# MJ828_-_prod.net
KiCad netlist of a schematic drawn in EAGLE
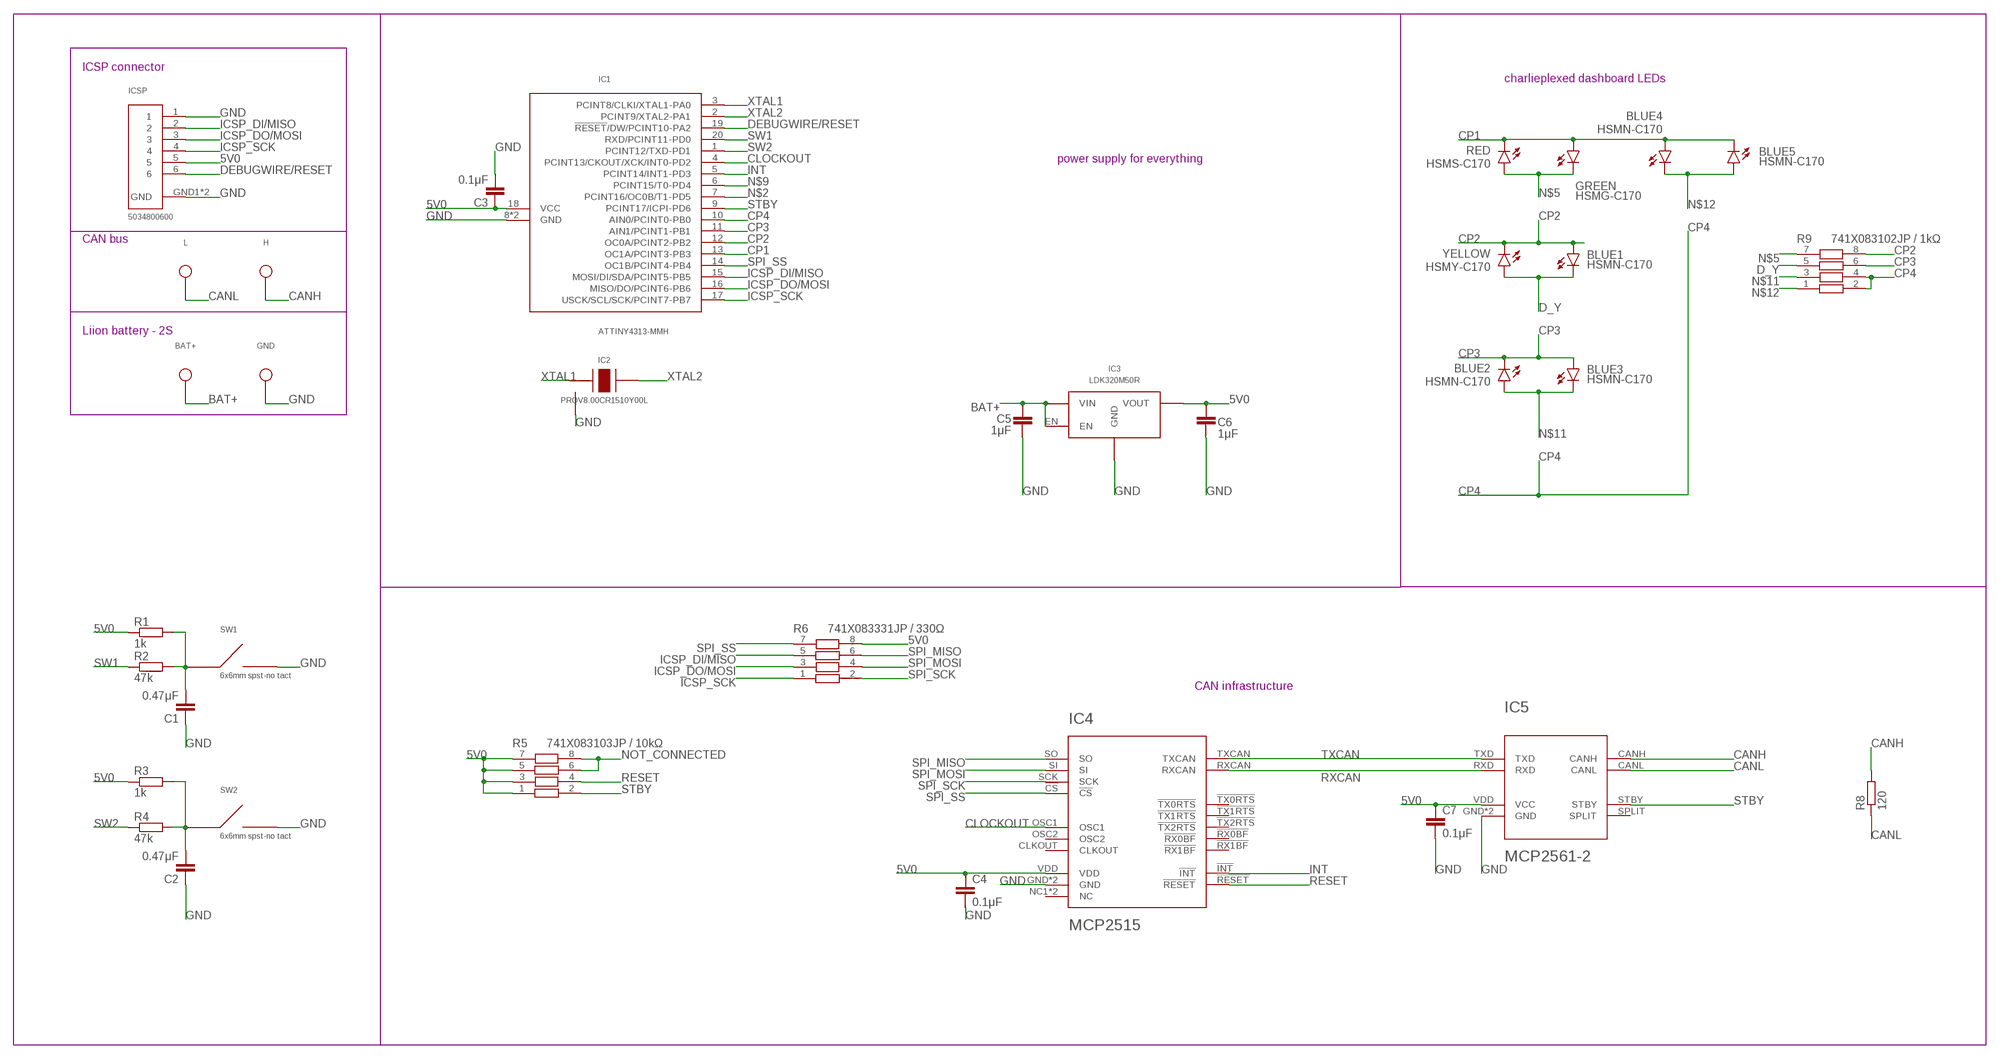
[diagram p0: schematic, sheet 1]

(export (version "E")
  (design (tool "Eeschema 10.0.6"))
  (components
    (comp (ref "BAT+")
      (value "8V4 Battery +")
      (footprint "eagle-import:TH-0.9MM")
      (libsource (lib "eagle-import") (part "TPTH-0.9MM"))
    )
    (comp (ref "BLUE1")
      (value "HSMN-C170")
      (footprint "eagle-import:SML0805")
      (libsource (lib "eagle-import") (part "LEDSML0805"))
    )
    (comp (ref "BLUE2")
      (value "HSMN-C170")
      (footprint "eagle-import:SML0805")
      (libsource (lib "eagle-import") (part "LEDSML0805"))
    )
    (comp (ref "BLUE3")
      (value "HSMN-C170")
      (footprint "eagle-import:SML0805")
      (libsource (lib "eagle-import") (part "LEDSML0805"))
    )
    (comp (ref "BLUE4")
      (value "HSMN-C170")
      (footprint "eagle-import:SML0805")
      (libsource (lib "eagle-import") (part "LEDSML0805"))
    )
    (comp (ref "BLUE5")
      (value "HSMN-C170")
      (footprint "eagle-import:SML0805")
      (libsource (lib "eagle-import") (part "LEDSML0805"))
    )
    (comp (ref "C1")
      (value "0.47μF")
      (footprint "eagle-import:C0402")
      (libsource (lib "eagle-import") (part "C-EUC0402"))
    )
    (comp (ref "C2")
      (value "0.47μF")
      (footprint "eagle-import:C0402")
      (libsource (lib "eagle-import") (part "C-EUC0402"))
    )
    (comp (ref "C3")
      (value "0.1μF")
      (footprint "eagle-import:C0402")
      (libsource (lib "eagle-import") (part "C-EUC0402"))
    )
    (comp (ref "C4")
      (value "0.1μF")
      (footprint "eagle-import:C0402")
      (libsource (lib "eagle-import") (part "C-EUC0402"))
    )
    (comp (ref "C5")
      (value "1μF")
      (footprint "eagle-import:C0402")
      (libsource (lib "eagle-import") (part "C-EUC0402"))
    )
    (comp (ref "C6")
      (value "1μF")
      (footprint "eagle-import:C0402")
      (libsource (lib "eagle-import") (part "C-EUC0402"))
    )
    (comp (ref "C7")
      (value "0.1μF")
      (footprint "eagle-import:C0402")
      (libsource (lib "eagle-import") (part "C-EUC0402"))
    )
    (comp (ref "GND")
      (value "Ground")
      (footprint "eagle-import:TH-0.9MM")
      (libsource (lib "eagle-import") (part "TPTH-0.9MM"))
    )
    (comp (ref "GREEN")
      (value "HSMG-C170")
      (footprint "eagle-import:SML0805")
      (libsource (lib "eagle-import") (part "LEDSML0805"))
    )
    (comp (ref "H")
      (value "CAN High")
      (footprint "eagle-import:TH-0.9MM")
      (libsource (lib "eagle-import") (part "TPTH-0.9MM"))
    )
    (comp (ref "IC1")
      (value "ATTINY4313-MMH")
      (footprint "eagle-import:VQFN-20")
      (fields (field (name "SPICEPREFIX") "X"))
      (libsource (lib "eagle-import") (part "ATTINY4313VQFN-20"))
    )
    (comp (ref "IC2")
      (value "PRQV8.00CR1510Y00L")
      (footprint "eagle-import:SMT")
      (libsource (lib "eagle-import") (part "PRQV"))
    )
    (comp (ref "IC3")
      (value "LDK320M50R")
      (footprint "eagle-import:SOT-23-5L")
      (libsource (lib "eagle-import") (part "LDK320SOT-23-5L"))
    )
    (comp (ref "IC4")
      (value "MCP2515")
      (footprint "eagle-import:QFN20")
      (libsource (lib "eagle-import") (part "MCP2515-I-ML"))
    )
    (comp (ref "IC5")
      (value "MCP2561-2")
      (footprint "eagle-import:DFN10")
      (libsource (lib "eagle-import") (part "MCP2561-2"))
    )
    (comp (ref "ICSP")
      (value "5034800600")
      (footprint "eagle-import:SMT")
      (libsource (lib "eagle-import") (part "5034800600"))
    )
    (comp (ref "L")
      (value "CAN Low")
      (footprint "eagle-import:TH-0.9MM")
      (libsource (lib "eagle-import") (part "TPTH-0.9MM"))
    )
    (comp (ref "R1")
      (value "1k")
      (footprint "eagle-import:R0402")
      (libsource (lib "eagle-import") (part "R-EU_R0402"))
    )
    (comp (ref "R2")
      (value "47k")
      (footprint "eagle-import:R0402")
      (libsource (lib "eagle-import") (part "R-EU_R0402"))
    )
    (comp (ref "R3")
      (value "1k")
      (footprint "eagle-import:R0402")
      (libsource (lib "eagle-import") (part "R-EU_R0402"))
    )
    (comp (ref "R4")
      (value "47k")
      (footprint "eagle-import:R0402")
      (libsource (lib "eagle-import") (part "R-EU_R0402"))
    )
    (comp (ref "R5")
      (value "741X083103JP / 10kΩ")
      (footprint "eagle-import:0402")
      (libsource (lib "eagle-import") (part "741X083331JP"))
    )
    (comp (ref "R6")
      (value "741X083331JP / 330Ω")
      (footprint "eagle-import:0402")
      (libsource (lib "eagle-import") (part "741X083331JP"))
    )
    (comp (ref "R8")
      (value "120")
      (footprint "eagle-import:R0402")
      (libsource (lib "eagle-import") (part "R-EU_R0402"))
    )
    (comp (ref "R9")
      (value "741X083102JP / 1kΩ")
      (footprint "eagle-import:0402")
      (libsource (lib "eagle-import") (part "741X083331JP"))
    )
    (comp (ref "RED")
      (value "HSMS-C170")
      (footprint "eagle-import:SML0805")
      (libsource (lib "eagle-import") (part "LEDSML0805"))
    )
    (comp (ref "SW1")
      (value "6x6mm spst-no tact")
      (footprint "eagle-import:SMD")
      (libsource (lib "eagle-import") (part "TL3305-844809"))
    )
    (comp (ref "SW2")
      (value "6x6mm spst-no tact")
      (footprint "eagle-import:SMD")
      (libsource (lib "eagle-import") (part "TL3305-844809"))
    )
    (comp (ref "YELLOW")
      (value "HSMY-C170")
      (footprint "eagle-import:SML0805")
      (libsource (lib "eagle-import") (part "LEDSML0805"))
    )
  )
  (nets
    (net (code "1") (name "/5V0") (class "Default")
      (node (ref "C3") (pin "1") (pinfunction "1_1") (pintype "passive"))
      (node (ref "C4") (pin "1") (pinfunction "1_1") (pintype "passive"))
      (node (ref "C6") (pin "2") (pinfunction "2_2") (pintype "passive"))
      (node (ref "C7") (pin "1") (pinfunction "1_1") (pintype "passive"))
      (node (ref "IC1") (pin "18") (pinfunction "VCC_18") (pintype "bidirectional"))
      (node (ref "IC3") (pin "OUT") (pinfunction "VOUT_OUT") (pintype "bidirectional"))
      (node (ref "IC4") (pin "VDD") (pinfunction "VDD_VDD") (pintype "power_in"))
      (node (ref "IC5") (pin "VDD") (pinfunction "VCC_VDD") (pintype "power_in"))
      (node (ref "ICSP") (pin "5") (pinfunction "5_5") (pintype "bidirectional"))
      (node (ref "R1") (pin "1") (pinfunction "1_1") (pintype "passive"))
      (node (ref "R3") (pin "1") (pinfunction "1_1") (pintype "passive"))
      (node (ref "R5") (pin "1") (pinfunction "1_1") (pintype "bidirectional"))
      (node (ref "R5") (pin "3") (pinfunction "3_3") (pintype "bidirectional"))
      (node (ref "R5") (pin "5") (pinfunction "5_5") (pintype "bidirectional"))
      (node (ref "R5") (pin "7") (pinfunction "7_7") (pintype "bidirectional"))
      (node (ref "R6") (pin "8") (pinfunction "8_8") (pintype "bidirectional"))
    )
    (net (code "2") (name "/BAT+") (class "Default")
      (node (ref "BAT+") (pin "TP$1") (pinfunction "TP$1_TP$1") (pintype "bidirectional"))
      (node (ref "C5") (pin "1") (pinfunction "1_1") (pintype "passive"))
      (node (ref "IC3") (pin "EN") (pinfunction "EN_EN") (pintype "bidirectional"))
      (node (ref "IC3") (pin "IN") (pinfunction "VIN_IN") (pintype "bidirectional"))
    )
    (net (code "3") (name "/CANH") (class "Default")
      (node (ref "H") (pin "TP$1") (pinfunction "TP$1_TP$1") (pintype "bidirectional"))
      (node (ref "IC5") (pin "CANH") (pinfunction "CANH_CANH") (pintype "bidirectional"))
      (node (ref "R8") (pin "2") (pinfunction "2_2") (pintype "passive"))
    )
    (net (code "4") (name "/CANL") (class "Default")
      (node (ref "IC5") (pin "CANL") (pinfunction "CANL_CANL") (pintype "bidirectional"))
      (node (ref "L") (pin "TP$1") (pinfunction "TP$1_TP$1") (pintype "bidirectional"))
      (node (ref "R8") (pin "1") (pinfunction "1_1") (pintype "passive"))
    )
    (net (code "5") (name "/CLOCKOUT") (class "Default")
      (node (ref "IC1") (pin "4") (pinfunction "PCINT13/CKOUT/XCK/INT0-PD2_4") (pintype "bidirectional"))
      (node (ref "IC4") (pin "OSC1") (pinfunction "OSC1_OSC1") (pintype "bidirectional"))
    )
    (net (code "6") (name "/CP1") (class "Default")
      (node (ref "BLUE4") (pin "A") (pinfunction "A_A") (pintype "passive"))
      (node (ref "BLUE5") (pin "C") (pinfunction "C_C") (pintype "passive"))
      (node (ref "GREEN") (pin "A") (pinfunction "A_A") (pintype "passive"))
      (node (ref "IC1") (pin "13") (pinfunction "OC1A/PCINT3-PB3_13") (pintype "bidirectional"))
      (node (ref "RED") (pin "C") (pinfunction "C_C") (pintype "passive"))
    )
    (net (code "7") (name "/CP2") (class "Default")
      (node (ref "BLUE1") (pin "A") (pinfunction "A_A") (pintype "passive"))
      (node (ref "IC1") (pin "12") (pinfunction "OC0A/PCINT2-PB2_12") (pintype "bidirectional"))
      (node (ref "R9") (pin "8") (pinfunction "8_8") (pintype "bidirectional"))
      (node (ref "YELLOW") (pin "C") (pinfunction "C_C") (pintype "passive"))
    )
    (net (code "8") (name "/CP3") (class "Default")
      (node (ref "BLUE2") (pin "C") (pinfunction "C_C") (pintype "passive"))
      (node (ref "BLUE3") (pin "A") (pinfunction "A_A") (pintype "passive"))
      (node (ref "IC1") (pin "11") (pinfunction "AIN1/PCINT1-PB1_11") (pintype "bidirectional"))
      (node (ref "R9") (pin "6") (pinfunction "6_6") (pintype "bidirectional"))
    )
    (net (code "9") (name "/CP4") (class "Default")
      (node (ref "IC1") (pin "10") (pinfunction "AIN0/PCINT0-PB0_10") (pintype "bidirectional"))
      (node (ref "R9") (pin "2") (pinfunction "2_2") (pintype "bidirectional"))
      (node (ref "R9") (pin "4") (pinfunction "4_4") (pintype "bidirectional"))
    )
    (net (code "10") (name "/DEBUGWIRE{slash}RESET") (class "Default")
      (node (ref "IC1") (pin "19") (pinfunction "~{RESET}/DW/PCINT10-PA2_19") (pintype "bidirectional"))
      (node (ref "ICSP") (pin "6") (pinfunction "6_6") (pintype "bidirectional"))
    )
    (net (code "11") (name "/D_Y") (class "Default")
      (node (ref "BLUE1") (pin "C") (pinfunction "C_C") (pintype "passive"))
      (node (ref "R9") (pin "5") (pinfunction "5_5") (pintype "bidirectional"))
      (node (ref "YELLOW") (pin "A") (pinfunction "A_A") (pintype "passive"))
    )
    (net (code "12") (name "/GND") (class "Default")
      (node (ref "C1") (pin "1") (pinfunction "1_1") (pintype "passive"))
      (node (ref "C2") (pin "1") (pinfunction "1_1") (pintype "passive"))
      (node (ref "C3") (pin "2") (pinfunction "2_2") (pintype "passive"))
      (node (ref "C4") (pin "2") (pinfunction "2_2") (pintype "passive"))
      (node (ref "C5") (pin "2") (pinfunction "2_2") (pintype "passive"))
      (node (ref "C6") (pin "1") (pinfunction "1_1") (pintype "passive"))
      (node (ref "C7") (pin "2") (pinfunction "2_2") (pintype "passive"))
      (node (ref "GND") (pin "TP$1") (pinfunction "TP$1_TP$1") (pintype "bidirectional"))
      (node (ref "IC1") (pin "8") (pinfunction "GND_8") (pintype "bidirectional"))
      (node (ref "IC1") (pin "GND") (pinfunction "GND_GND") (pintype "bidirectional"))
      (node (ref "IC2") (pin "GND") (pinfunction "GND_GND") (pintype "bidirectional"))
      (node (ref "IC3") (pin "GND") (pinfunction "GND_GND") (pintype "bidirectional"))
      (node (ref "IC4") (pin "GND") (pinfunction "GND_GND") (pintype "power_in"))
      (node (ref "IC4") (pin "GND6") (pinfunction "GND_GND6") (pintype "power_in"))
      (node (ref "IC5") (pin "GND") (pinfunction "GND_GND") (pintype "power_in"))
      (node (ref "IC5") (pin "VSS") (pinfunction "GND_VSS") (pintype "power_in"))
      (node (ref "ICSP") (pin "1") (pinfunction "1_1") (pintype "bidirectional"))
      (node (ref "ICSP") (pin "GND1") (pinfunction "GND_GND1") (pintype "bidirectional"))
      (node (ref "ICSP") (pin "GND2") (pinfunction "GND_GND2") (pintype "bidirectional"))
      (node (ref "SW1") (pin "3") (pinfunction "P$2_3") (pintype "bidirectional"))
      (node (ref "SW1") (pin "4") (pinfunction "P$2_4") (pintype "bidirectional"))
      (node (ref "SW2") (pin "3") (pinfunction "P$2_3") (pintype "bidirectional"))
      (node (ref "SW2") (pin "4") (pinfunction "P$2_4") (pintype "bidirectional"))
    )
    (net (code "13") (name "/ICSP_DI{slash}MISO") (class "Default")
      (node (ref "IC1") (pin "15") (pinfunction "MOSI/DI/SDA/PCINT5-PB5_15") (pintype "bidirectional"))
      (node (ref "ICSP") (pin "2") (pinfunction "2_2") (pintype "bidirectional"))
      (node (ref "R6") (pin "5") (pinfunction "5_5") (pintype "bidirectional"))
    )
    (net (code "14") (name "/ICSP_DO{slash}MOSI") (class "Default")
      (node (ref "IC1") (pin "16") (pinfunction "MISO/DO/PCINT6-PB6_16") (pintype "bidirectional"))
      (node (ref "ICSP") (pin "3") (pinfunction "3_3") (pintype "bidirectional"))
      (node (ref "R6") (pin "3") (pinfunction "3_3") (pintype "bidirectional"))
    )
    (net (code "15") (name "/ICSP_SCK") (class "Default")
      (node (ref "IC1") (pin "17") (pinfunction "USCK/SCL/SCK/PCINT7-PB7_17") (pintype "bidirectional"))
      (node (ref "ICSP") (pin "4") (pinfunction "4_4") (pintype "bidirectional"))
      (node (ref "R6") (pin "1") (pinfunction "1_1") (pintype "bidirectional"))
    )
    (net (code "16") (name "/INT") (class "Default")
      (node (ref "IC1") (pin "5") (pinfunction "PCINT14/INT1-PD3_5") (pintype "bidirectional"))
      (node (ref "IC4") (pin "!INT!") (pinfunction "~{INT}_!INT!") (pintype "bidirectional"))
    )
    (net (code "17") (name "/N$2") (class "Default")
      (node (ref "IC1") (pin "7") (pinfunction "PCINT16/OC0B/T1-PD5_7") (pintype "bidirectional"))
    )
    (net (code "18") (name "/N$5") (class "Default")
      (node (ref "GREEN") (pin "C") (pinfunction "C_C") (pintype "passive"))
      (node (ref "R9") (pin "7") (pinfunction "7_7") (pintype "bidirectional"))
      (node (ref "RED") (pin "A") (pinfunction "A_A") (pintype "passive"))
    )
    (net (code "19") (name "/N$9") (class "Default")
      (node (ref "IC1") (pin "6") (pinfunction "PCINT15/T0-PD4_6") (pintype "bidirectional"))
    )
    (net (code "20") (name "/N$11") (class "Default")
      (node (ref "BLUE2") (pin "A") (pinfunction "A_A") (pintype "passive"))
      (node (ref "BLUE3") (pin "C") (pinfunction "C_C") (pintype "passive"))
      (node (ref "R9") (pin "3") (pinfunction "3_3") (pintype "bidirectional"))
    )
    (net (code "21") (name "/N$12") (class "Default")
      (node (ref "BLUE4") (pin "C") (pinfunction "C_C") (pintype "passive"))
      (node (ref "BLUE5") (pin "A") (pinfunction "A_A") (pintype "passive"))
      (node (ref "R9") (pin "1") (pinfunction "1_1") (pintype "bidirectional"))
    )
    (net (code "22") (name "/NOT_CONNECTED") (class "Default")
      (node (ref "R5") (pin "6") (pinfunction "6_6") (pintype "bidirectional"))
      (node (ref "R5") (pin "8") (pinfunction "8_8") (pintype "bidirectional"))
    )
    (net (code "23") (name "/RESET") (class "Default")
      (node (ref "IC4") (pin "!RESET!") (pinfunction "~{RESET}_!RESET!") (pintype "bidirectional"))
      (node (ref "R5") (pin "4") (pinfunction "4_4") (pintype "bidirectional"))
    )
    (net (code "24") (name "/RXCAN") (class "Default")
      (node (ref "IC4") (pin "RXCAN") (pinfunction "RXCAN_RXCAN") (pintype "input"))
      (node (ref "IC5") (pin "RXD") (pinfunction "RXD_RXD") (pintype "output"))
    )
    (net (code "25") (name "/SPI_MISO") (class "Default")
      (node (ref "IC4") (pin "SO") (pinfunction "SO_SO") (pintype "output"))
      (node (ref "R6") (pin "6") (pinfunction "6_6") (pintype "bidirectional"))
    )
    (net (code "26") (name "/SPI_MOSI") (class "Default")
      (node (ref "IC4") (pin "SI") (pinfunction "SI_SI") (pintype "input"))
      (node (ref "R6") (pin "4") (pinfunction "4_4") (pintype "bidirectional"))
    )
    (net (code "27") (name "/SPI_SCK") (class "Default")
      (node (ref "IC4") (pin "SCK") (pinfunction "SCK_SCK") (pintype "bidirectional"))
      (node (ref "R6") (pin "2") (pinfunction "2_2") (pintype "bidirectional"))
    )
    (net (code "28") (name "/SPI_SS") (class "Default")
      (node (ref "IC1") (pin "14") (pinfunction "OC1B/PCINT4-PB4_14") (pintype "bidirectional"))
      (node (ref "IC4") (pin "!CS!") (pinfunction "~{CS}_!CS!") (pintype "bidirectional"))
      (node (ref "R6") (pin "7") (pinfunction "7_7") (pintype "bidirectional"))
    )
    (net (code "29") (name "/STBY") (class "Default")
      (node (ref "IC1") (pin "9") (pinfunction "PCINT17/ICPI-PD6_9") (pintype "bidirectional"))
      (node (ref "IC5") (pin "STBY") (pinfunction "STBY_STBY") (pintype "bidirectional"))
      (node (ref "R5") (pin "2") (pinfunction "2_2") (pintype "bidirectional"))
    )
    (net (code "30") (name "/SW1") (class "Default")
      (node (ref "IC1") (pin "20") (pinfunction "RXD/PCINT11-PD0_20") (pintype "bidirectional"))
      (node (ref "R2") (pin "1") (pinfunction "1_1") (pintype "passive"))
    )
    (net (code "31") (name "/SW2") (class "Default")
      (node (ref "IC1") (pin "1") (pinfunction "PCINT12/TXD-PD1_1") (pintype "bidirectional"))
      (node (ref "R4") (pin "1") (pinfunction "1_1") (pintype "passive"))
    )
    (net (code "32") (name "/TXCAN") (class "Default")
      (node (ref "IC4") (pin "TXCAN") (pinfunction "TXCAN_TXCAN") (pintype "output"))
      (node (ref "IC5") (pin "TXD") (pinfunction "TXD_TXD") (pintype "input"))
    )
    (net (code "33") (name "/XTAL1") (class "Default")
      (node (ref "IC1") (pin "3") (pinfunction "PCINT8/CLKI/XTAL1-PA0_3") (pintype "bidirectional"))
      (node (ref "IC2") (pin "XTAL1") (pinfunction "XTAL1_XTAL1") (pintype "bidirectional"))
    )
    (net (code "34") (name "/XTAL2") (class "Default")
      (node (ref "IC1") (pin "2") (pinfunction "PCINT9/XTAL2-PA1_2") (pintype "bidirectional"))
      (node (ref "IC2") (pin "XTAL2") (pinfunction "XTAL2_XTAL2") (pintype "bidirectional"))
    )
    (net (code "35") (name "Net-(C1-Pad2)") (class "Default")
      (node (ref "C1") (pin "2") (pinfunction "2_2") (pintype "passive"))
      (node (ref "R1") (pin "2") (pinfunction "2_2") (pintype "passive"))
      (node (ref "R2") (pin "2") (pinfunction "2_2") (pintype "passive"))
      (node (ref "SW1") (pin "1") (pinfunction "P$1_1") (pintype "bidirectional"))
      (node (ref "SW1") (pin "2") (pinfunction "P$1_2") (pintype "bidirectional"))
    )
    (net (code "36") (name "Net-(C2-Pad2)") (class "Default")
      (node (ref "C2") (pin "2") (pinfunction "2_2") (pintype "passive"))
      (node (ref "R3") (pin "2") (pinfunction "2_2") (pintype "passive"))
      (node (ref "R4") (pin "2") (pinfunction "2_2") (pintype "passive"))
      (node (ref "SW2") (pin "1") (pinfunction "P$1_1") (pintype "bidirectional"))
      (node (ref "SW2") (pin "2") (pinfunction "P$1_2") (pintype "bidirectional"))
    )
    (net (code "37") (name "unconnected-(IC4-NC-PadNC1)") (class "Default")
      (node (ref "IC4") (pin "NC1") (pinfunction "NC_NC1") (pintype "no_connect"))
    )
    (net (code "38") (name "unconnected-(IC4-NC-PadNC2)") (class "Default")
      (node (ref "IC4") (pin "NC2") (pinfunction "NC_NC2") (pintype "no_connect"))
    )
    (net (code "39") (name "unconnected-(IC4-PadCLKOUT)") (class "Default")
      (node (ref "IC4") (pin "CLKOUT") (pinfunction "CLKOUT_CLKOUT") (pintype "bidirectional"))
    )
    (net (code "40") (name "unconnected-(IC4-PadOSC2)") (class "Default")
      (node (ref "IC4") (pin "OSC2") (pinfunction "OSC2_OSC2") (pintype "bidirectional"))
    )
    (net (code "41") (name "unconnected-(IC4-~{RX0BF}-Pad!RX0BF!)") (class "Default")
      (node (ref "IC4") (pin "!RX0BF!") (pinfunction "~{RX0BF}_!RX0BF!") (pintype "bidirectional"))
    )
    (net (code "42") (name "unconnected-(IC4-~{RX1BF}-Pad!RX1BF!)") (class "Default")
      (node (ref "IC4") (pin "!RX1BF!") (pinfunction "~{RX1BF}_!RX1BF!") (pintype "bidirectional"))
    )
    (net (code "43") (name "unconnected-(IC4-~{TX0RTS}-Pad!TX0RTS!)") (class "Default")
      (node (ref "IC4") (pin "!TX0RTS!") (pinfunction "~{TX0RTS}_!TX0RTS!") (pintype "bidirectional"))
    )
    (net (code "44") (name "unconnected-(IC4-~{TX1RTS}-Pad!TX1RTS!)") (class "Default")
      (node (ref "IC4") (pin "!TX1RTS!") (pinfunction "~{TX1RTS}_!TX1RTS!") (pintype "bidirectional"))
    )
    (net (code "45") (name "unconnected-(IC4-~{TX2RTS}-Pad!TX2RTS!)") (class "Default")
      (node (ref "IC4") (pin "!TX2RTS!") (pinfunction "~{TX2RTS}_!TX2RTS!") (pintype "bidirectional"))
    )
    (net (code "46") (name "unconnected-(IC5-PadSPLIT)") (class "Default")
      (node (ref "IC5") (pin "SPLIT") (pinfunction "SPLIT_SPLIT") (pintype "bidirectional"))
    )
  )
)
